# 5_ESP_01.net
KiCad netlist of a schematic drawn in Altium Designer
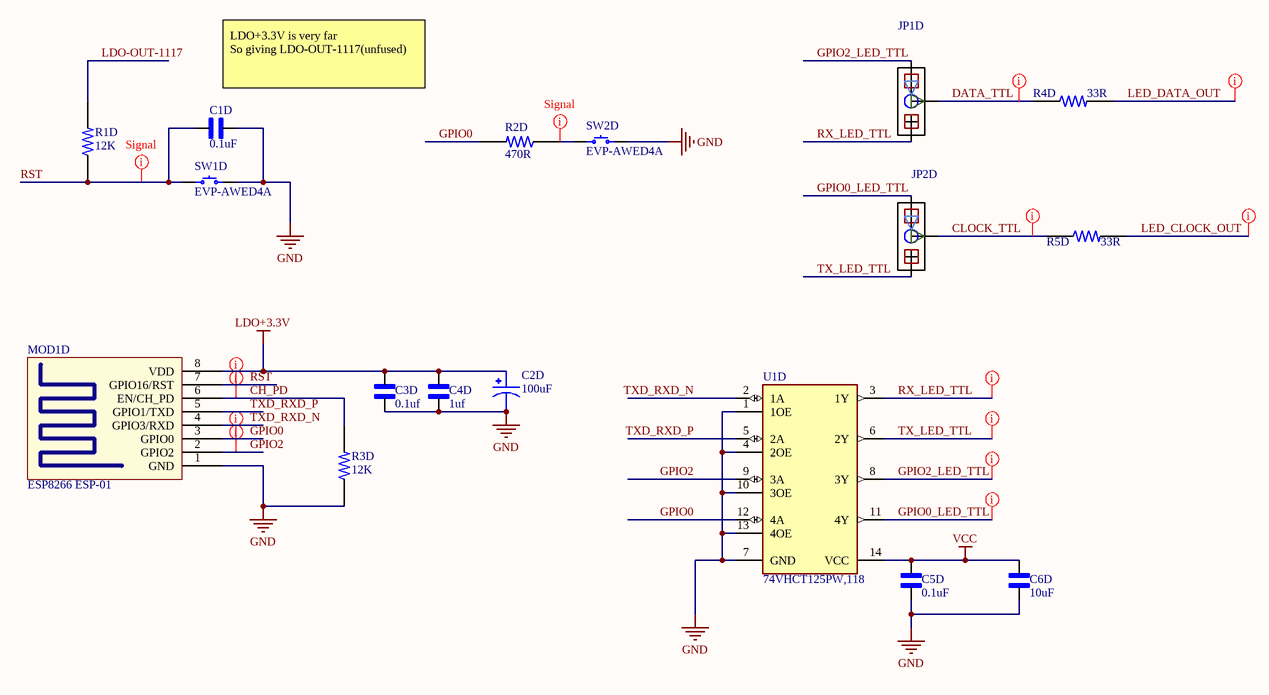
[diagram p0: 5_ESP_01.SchDoc]

(export (version "E")
  (design (tool "Eeschema 10.0.6"))
  (components
    (comp (ref "C1D")
      (value "0.1uF")
      (footprint "C-0603")
      (description "Ceramic Capacitor 16V 0603 (1608 Metric)")
      (fields (field (name "MP") "C0603C104J4RAC") (field (name "MF") "KEMET"))
      (libsource (lib "") (part "C-0603_1"))
    )
    (comp (ref "C2D")
      (value "100uF")
      (footprint "1411-3528")
      (description "Molded Tantalum Capacitors 16V 1411 (3528 Metric)")
      (fields (field (name "MF") "KEMET") (field (name "MP") "T495B106K025ATE750"))
      (libsource (lib "ESP01-S-UART") (part "C-1411 (3528 Metric)"))
    )
    (comp (ref "C3D")
      (value "0.1uf")
      (footprint "C-0603")
      (description "Ceramic Capacitor 16V 0603 (1608 Metric)")
      (fields (field (name "MP") "C0603C104J4RAC") (field (name "MF") "KEMET"))
      (libsource (lib "ESP01-S-UART") (part "C-0603"))
    )
    (comp (ref "C4D")
      (value "1uf")
      (footprint "C-0603")
      (description "Ceramic Capacitor 16V 0603 (1608 Metric)")
      (fields (field (name "MP") "C0603C104J4RAC") (field (name "MF") "KEMET"))
      (libsource (lib "ESP01-S-UART") (part "C-0603"))
    )
    (comp (ref "C5D")
      (value "0.1uF")
      (footprint "C-0603")
      (description "Ceramic Capacitor 16V 0603 (1608 Metric)")
      (fields (field (name "MP") "C0603C104J4RAC") (field (name "MF") "KEMET"))
      (libsource (lib "ESP01-S-UART") (part "C-0603"))
    )
    (comp (ref "C6D")
      (value "10uF")
      (footprint "C-0603")
      (description "Ceramic Capacitor 16V 0603 (1608 Metric)")
      (fields (field (name "MP") "C0603C104J4RAC") (field (name "MF") "KEMET"))
      (libsource (lib "ESP01-S-UART") (part "C-0603"))
    )
    (comp (ref "JP1D")
      (value "Solder Pad")
      (footprint "Solder_Pad_3_Pin_NC_Medium")
      (description "Solder Pad 3 Pin NC 1.016 mm Pitch")
      (libsource (lib "ESP01-S-UART") (part "Solder_Pad_3_Pin_NC_Medium"))
    )
    (comp (ref "JP2D")
      (value "Solder Pad")
      (footprint "Solder_Pad_3_Pin_NC_Medium")
      (description "Solder Pad 3 Pin NC 1.016 mm Pitch")
      (libsource (lib "ESP01-S-UART") (part "Solder_Pad_3_Pin_NC_Medium"))
    )
    (comp (ref "MOD1D")
      (value "ESP8266 ESP-01")
      (footprint "ESP8266:ESP8266 ESP-01")
      (libsource (lib "ESP01-S-UART") (part "ESP8266 ESP-01"))
    )
    (comp (ref "R1D")
      (value "12K")
      (footprint "R-0603")
      (description "0603")
      (fields (field (name "MP") "2-1623703-0") (field (name "TOLERANCE") "1%"))
      (libsource (lib "ESP01-S-UART") (part "R-0603"))
    )
    (comp (ref "R2D")
      (value "470R")
      (footprint "R-0603")
      (description "0603")
      (fields (field (name "MP") "2-1623703-0") (field (name "TOLERANCE") "1%"))
      (libsource (lib "ESP01-S-UART") (part "R-0603"))
    )
    (comp (ref "R3D")
      (value "12K")
      (footprint "R-0603")
      (description "0603")
      (fields (field (name "MP") "2-1623703-0") (field (name "TOLERANCE") "1%"))
      (libsource (lib "ESP01-S-UART") (part "R-0603"))
    )
    (comp (ref "R4D")
      (value "33R")
      (footprint "R-0603")
      (description "0603")
      (fields (field (name "MP") "2-1623703-0") (field (name "TOLERANCE") "1%"))
      (libsource (lib "ESP01-S-UART") (part "R-0603"))
    )
    (comp (ref "R5D")
      (value "33R")
      (footprint "R-0603")
      (description "0603")
      (fields (field (name "MP") "2-1623703-0") (field (name "TOLERANCE") "1%"))
      (libsource (lib "ESP01-S-UART") (part "R-0603"))
    )
    (comp (ref "SW1D")
      (value "EVP-AWED4A")
      (footprint "PANASONIC EVPAW")
      (description "3.0MM X 2.0MM / 3.3N / 0.15MM ST")
      (fields (field (name "MANUFACTURER") "Panasonic Electronic Components"))
      (libsource (lib "ESP01-S-UART") (part "SPST-NO 2 PIN"))
    )
    (comp (ref "SW2D")
      (value "EVP-AWED4A")
      (footprint "PANASONIC EVPAW")
      (description "3.0MM X 2.0MM / 3.3N / 0.15MM ST")
      (fields (field (name "MANUFACTURER") "Panasonic Electronic Components"))
      (libsource (lib "ESP01-S-UART") (part "SPST-NO 2 PIN"))
    )
    (comp (ref "U1D")
      (value "74VHCT125PW,118")
      (footprint "Custom-IC:SOP65P640X110-14N")
      (description "Buffer, Non-Inverting 4 Element 1 Bit per Element 3-State Output 14-SOIC")
      (fields (field (name "MP") "74HC125") (field (name "MF") "Nexperia USA"))
      (libsource (lib "ESP01-S-UART") (part "74VHCT125PW,118"))
    )
  )
  (nets
    (net (code "1") (name "/CH_PD") (class "Default")
      (node (ref "MOD1D") (pin "6") (pinfunction "EN/CH_PD_6") (pintype "passive"))
      (node (ref "R3D") (pin "2") (pinfunction "2_2") (pintype "passive"))
    )
    (net (code "2") (name "/CLOCK_TTL") (class "Default")
      (node (ref "JP2D") (pin "2") (pinfunction "2_2") (pintype "passive"))
      (node (ref "R5D") (pin "1") (pinfunction "1_1") (pintype "passive"))
    )
    (net (code "3") (name "/DATA_TTL") (class "Default")
      (node (ref "JP1D") (pin "2") (pinfunction "2_2") (pintype "passive"))
      (node (ref "R4D") (pin "1") (pinfunction "1_1") (pintype "passive"))
    )
    (net (code "4") (name "/GPIO0") (class "Default")
      (node (ref "MOD1D") (pin "3") (pinfunction "GPIO0_3") (pintype "passive"))
      (node (ref "R2D") (pin "2") (pinfunction "2_2") (pintype "passive"))
      (node (ref "U1D") (pin "12") (pinfunction "4A_12") (pintype "bidirectional"))
    )
    (net (code "5") (name "/GPIO0_LED_TTL") (class "Default")
      (node (ref "JP2D") (pin "1") (pinfunction "1_1") (pintype "passive"))
      (node (ref "U1D") (pin "11") (pinfunction "4Y_11") (pintype "output"))
    )
    (net (code "6") (name "/GPIO2") (class "Default")
      (node (ref "MOD1D") (pin "2") (pinfunction "GPIO2_2") (pintype "passive"))
      (node (ref "U1D") (pin "9") (pinfunction "3A_9") (pintype "bidirectional"))
    )
    (net (code "7") (name "/GPIO2_LED_TTL") (class "Default")
      (node (ref "JP1D") (pin "1") (pinfunction "1_1") (pintype "passive"))
      (node (ref "U1D") (pin "8") (pinfunction "3Y_8") (pintype "output"))
    )
    (net (code "8") (name "/LDO-OUT-1117") (class "Default")
      (node (ref "R1D") (pin "2") (pinfunction "2_2") (pintype "passive"))
    )
    (net (code "9") (name "/LED_CLOCK_OUT") (class "Default")
      (node (ref "R5D") (pin "2") (pinfunction "2_2") (pintype "passive"))
    )
    (net (code "10") (name "/LED_DATA_OUT") (class "Default")
      (node (ref "R4D") (pin "2") (pinfunction "2_2") (pintype "passive"))
    )
    (net (code "11") (name "/RST") (class "Default")
      (node (ref "C1D") (pin "1") (pinfunction "1_1") (pintype "passive"))
      (node (ref "MOD1D") (pin "7") (pinfunction "GPIO16/RST_7") (pintype "passive"))
      (node (ref "R1D") (pin "1") (pinfunction "1_1") (pintype "passive"))
      (node (ref "SW1D") (pin "1") (pinfunction "1_1") (pintype "passive"))
    )
    (net (code "12") (name "/RX_LED_TTL") (class "Default")
      (node (ref "JP1D") (pin "3") (pinfunction "3_3") (pintype "passive"))
      (node (ref "U1D") (pin "3") (pinfunction "1Y_3") (pintype "output"))
    )
    (net (code "13") (name "/TXD_RXD_N") (class "Default")
      (node (ref "MOD1D") (pin "4") (pinfunction "GPIO3/RXD_4") (pintype "passive"))
      (node (ref "U1D") (pin "2") (pinfunction "1A_2") (pintype "bidirectional"))
    )
    (net (code "14") (name "/TXD_RXD_P") (class "Default")
      (node (ref "MOD1D") (pin "5") (pinfunction "GPIO1/TXD_5") (pintype "passive"))
      (node (ref "U1D") (pin "5") (pinfunction "2A_5") (pintype "bidirectional"))
    )
    (net (code "15") (name "/TX_LED_TTL") (class "Default")
      (node (ref "JP2D") (pin "3") (pinfunction "3_3") (pintype "passive"))
      (node (ref "U1D") (pin "6") (pinfunction "2Y_6") (pintype "output"))
    )
    (net (code "16") (name "GND") (class "Default")
      (node (ref "C1D") (pin "2") (pinfunction "2_2") (pintype "passive"))
      (node (ref "C2D") (pin "2") (pinfunction "2_2") (pintype "passive"))
      (node (ref "C3D") (pin "1") (pinfunction "1_1") (pintype "passive"))
      (node (ref "C4D") (pin "1") (pinfunction "1_1") (pintype "passive"))
      (node (ref "C5D") (pin "1") (pinfunction "1_1") (pintype "passive"))
      (node (ref "C6D") (pin "1") (pinfunction "1_1") (pintype "passive"))
      (node (ref "MOD1D") (pin "1") (pinfunction "GND_1") (pintype "passive"))
      (node (ref "R3D") (pin "1") (pinfunction "1_1") (pintype "passive"))
      (node (ref "SW1D") (pin "2") (pinfunction "2_2") (pintype "passive"))
      (node (ref "SW2D") (pin "2") (pinfunction "2_2") (pintype "passive"))
      (node (ref "U1D") (pin "1") (pinfunction "1OE_1") (pintype "passive"))
      (node (ref "U1D") (pin "10") (pinfunction "3OE_10") (pintype "passive"))
      (node (ref "U1D") (pin "13") (pinfunction "4OE_13") (pintype "passive"))
      (node (ref "U1D") (pin "4") (pinfunction "2OE_4") (pintype "passive"))
      (node (ref "U1D") (pin "7") (pinfunction "GND_7") (pintype "power_in"))
    )
    (net (code "17") (name "LDO+3.3V") (class "Default")
      (node (ref "C2D") (pin "1") (pinfunction "1_1") (pintype "passive"))
      (node (ref "C3D") (pin "2") (pinfunction "2_2") (pintype "passive"))
      (node (ref "C4D") (pin "2") (pinfunction "2_2") (pintype "passive"))
      (node (ref "MOD1D") (pin "8") (pinfunction "VDD_8") (pintype "passive"))
    )
    (net (code "18") (name "Net-(R2D-Pad1)") (class "Default")
      (node (ref "R2D") (pin "1") (pinfunction "1_1") (pintype "passive"))
      (node (ref "SW2D") (pin "1") (pinfunction "1_1") (pintype "passive"))
    )
    (net (code "19") (name "VCC") (class "Default")
      (node (ref "C5D") (pin "2") (pinfunction "2_2") (pintype "passive"))
      (node (ref "C6D") (pin "2") (pinfunction "2_2") (pintype "passive"))
      (node (ref "U1D") (pin "14") (pinfunction "VCC_14") (pintype "power_in"))
    )
  )
)
